# ESPProgrammer.net
KiCad netlist of a schematic drawn in EAGLE
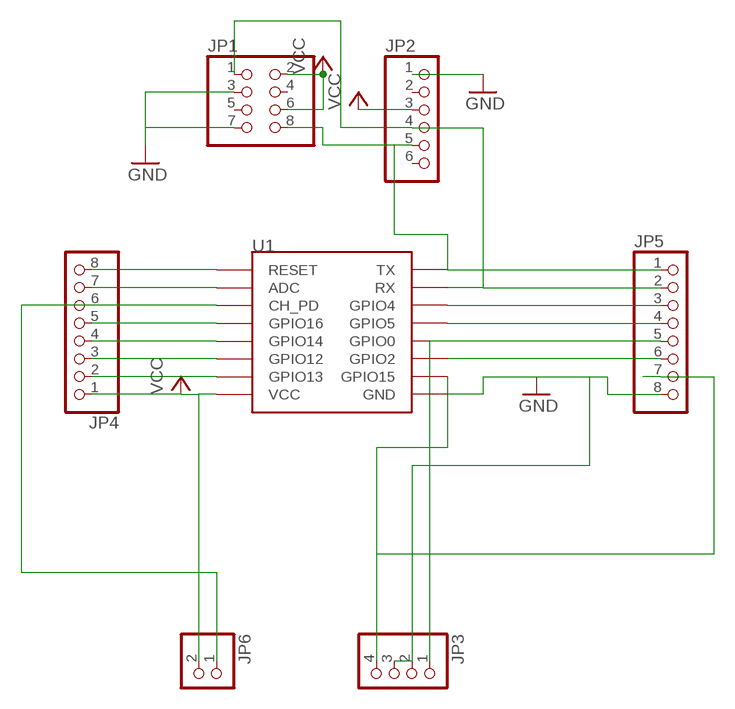
[diagram p0: schematic, sheet 1]

(export (version "E")
  (design (tool "Eeschema 10.0.6"))
  (components
    (comp (ref "JP1")
      (value "PINHD-2X4")
      (footprint "eagle-import:2X04")
      (libsource (lib "eagle-import") (part "PINHD-2X4"))
    )
    (comp (ref "JP2")
      (value "PINHD-1X6")
      (footprint "eagle-import:1X06")
      (libsource (lib "eagle-import") (part "PINHD-1X6"))
    )
    (comp (ref "JP3")
      (value "PINHD-1X4")
      (footprint "eagle-import:1X04")
      (libsource (lib "eagle-import") (part "PINHD-1X4"))
    )
    (comp (ref "JP4")
      (value "PINHD-1X8")
      (footprint "eagle-import:1X08")
      (libsource (lib "eagle-import") (part "PINHD-1X8"))
    )
    (comp (ref "JP5")
      (value "PINHD-1X8")
      (footprint "eagle-import:1X08")
      (libsource (lib "eagle-import") (part "PINHD-1X8"))
    )
    (comp (ref "JP6")
      (value "PINHD-1X2")
      (footprint "eagle-import:1X02")
      (libsource (lib "eagle-import") (part "PINHD-1X2"))
    )
    (comp (ref "U1")
      (value "ESP12")
      (footprint "eagle-import:ESP12")
      (libsource (lib "eagle-import") (part "ESP12"))
    )
  )
  (nets
    (net (code "1") (name "GND") (class "Default")
      (node (ref "JP1") (pin "3") (pinfunction "3_3") (pintype "passive"))
      (node (ref "JP1") (pin "7") (pinfunction "7_7") (pintype "passive"))
      (node (ref "JP2") (pin "1") (pinfunction "1_1") (pintype "passive"))
      (node (ref "JP3") (pin "2") (pinfunction "2_2") (pintype "passive"))
      (node (ref "JP3") (pin "3") (pinfunction "3_3") (pintype "passive"))
      (node (ref "JP5") (pin "8") (pinfunction "8_8") (pintype "passive"))
      (node (ref "U1") (pin "GND") (pinfunction "GND_GND") (pintype "bidirectional"))
    )
    (net (code "2") (name "Net-(JP1-Pad1)") (class "Default")
      (node (ref "JP1") (pin "1") (pinfunction "1_1") (pintype "passive"))
      (node (ref "JP2") (pin "4") (pinfunction "4_4") (pintype "passive"))
      (node (ref "JP5") (pin "2") (pinfunction "2_2") (pintype "passive"))
      (node (ref "U1") (pin "RX") (pinfunction "RX_RX") (pintype "bidirectional"))
    )
    (net (code "3") (name "Net-(JP1-Pad8)") (class "Default")
      (node (ref "JP1") (pin "8") (pinfunction "8_8") (pintype "passive"))
      (node (ref "JP2") (pin "5") (pinfunction "5_5") (pintype "passive"))
      (node (ref "JP5") (pin "1") (pinfunction "1_1") (pintype "passive"))
      (node (ref "U1") (pin "TX") (pinfunction "TX_TX") (pintype "bidirectional"))
    )
    (net (code "4") (name "Net-(JP3-Pad1)") (class "Default")
      (node (ref "JP3") (pin "1") (pinfunction "1_1") (pintype "passive"))
      (node (ref "JP5") (pin "5") (pinfunction "5_5") (pintype "passive"))
      (node (ref "U1") (pin "GPIO0") (pinfunction "GPIO0_GPIO0") (pintype "bidirectional"))
    )
    (net (code "5") (name "Net-(JP3-Pad4)") (class "Default")
      (node (ref "JP3") (pin "4") (pinfunction "4_4") (pintype "passive"))
      (node (ref "JP5") (pin "7") (pinfunction "7_7") (pintype "passive"))
      (node (ref "U1") (pin "GPIO15") (pinfunction "GPIO15_GPIO15") (pintype "bidirectional"))
    )
    (net (code "6") (name "Net-(JP4-Pad2)") (class "Default")
      (node (ref "JP4") (pin "2") (pinfunction "2_2") (pintype "passive"))
      (node (ref "U1") (pin "GPIO13") (pinfunction "GPIO13_GPIO13") (pintype "bidirectional"))
    )
    (net (code "7") (name "Net-(JP4-Pad3)") (class "Default")
      (node (ref "JP4") (pin "3") (pinfunction "3_3") (pintype "passive"))
      (node (ref "U1") (pin "GPIO12") (pinfunction "GPIO12_GPIO12") (pintype "bidirectional"))
    )
    (net (code "8") (name "Net-(JP4-Pad4)") (class "Default")
      (node (ref "JP4") (pin "4") (pinfunction "4_4") (pintype "passive"))
      (node (ref "U1") (pin "GPIO14") (pinfunction "GPIO14_GPIO14") (pintype "bidirectional"))
    )
    (net (code "9") (name "Net-(JP4-Pad5)") (class "Default")
      (node (ref "JP4") (pin "5") (pinfunction "5_5") (pintype "passive"))
      (node (ref "U1") (pin "GPIO16") (pinfunction "GPIO16_GPIO16") (pintype "bidirectional"))
    )
    (net (code "10") (name "Net-(JP4-Pad6)") (class "Default")
      (node (ref "JP4") (pin "6") (pinfunction "6_6") (pintype "passive"))
      (node (ref "JP6") (pin "1") (pinfunction "1_1") (pintype "passive"))
      (node (ref "U1") (pin "CH_PD") (pinfunction "CH_PD_CH_PD") (pintype "bidirectional"))
    )
    (net (code "11") (name "Net-(JP4-Pad7)") (class "Default")
      (node (ref "JP4") (pin "7") (pinfunction "7_7") (pintype "passive"))
      (node (ref "U1") (pin "ADC") (pinfunction "ADC_ADC") (pintype "bidirectional"))
    )
    (net (code "12") (name "Net-(JP4-Pad8)") (class "Default")
      (node (ref "JP4") (pin "8") (pinfunction "8_8") (pintype "passive"))
      (node (ref "U1") (pin "RESET") (pinfunction "RESET_RESET") (pintype "bidirectional"))
    )
    (net (code "13") (name "Net-(JP5-Pad3)") (class "Default")
      (node (ref "JP5") (pin "3") (pinfunction "3_3") (pintype "passive"))
      (node (ref "U1") (pin "GPIO4") (pinfunction "GPIO4_GPIO4") (pintype "bidirectional"))
    )
    (net (code "14") (name "Net-(JP5-Pad4)") (class "Default")
      (node (ref "JP5") (pin "4") (pinfunction "4_4") (pintype "passive"))
      (node (ref "U1") (pin "GPIO5") (pinfunction "GPIO5_GPIO5") (pintype "bidirectional"))
    )
    (net (code "15") (name "Net-(JP5-Pad6)") (class "Default")
      (node (ref "JP5") (pin "6") (pinfunction "6_6") (pintype "passive"))
      (node (ref "U1") (pin "GPIO2") (pinfunction "GPIO2_GPIO2") (pintype "bidirectional"))
    )
    (net (code "16") (name "VCC") (class "Default")
      (node (ref "JP1") (pin "2") (pinfunction "2_2") (pintype "passive"))
      (node (ref "JP1") (pin "6") (pinfunction "6_6") (pintype "passive"))
      (node (ref "JP2") (pin "3") (pinfunction "3_3") (pintype "passive"))
      (node (ref "JP4") (pin "1") (pinfunction "1_1") (pintype "passive"))
      (node (ref "JP6") (pin "2") (pinfunction "2_2") (pintype "passive"))
      (node (ref "U1") (pin "VCC") (pinfunction "VCC_VCC") (pintype "bidirectional"))
    )
    (net (code "17") (name "unconnected-(JP1-Pad4)") (class "Default")
      (node (ref "JP1") (pin "4") (pinfunction "4_4") (pintype "passive"))
    )
    (net (code "18") (name "unconnected-(JP1-Pad5)") (class "Default")
      (node (ref "JP1") (pin "5") (pinfunction "5_5") (pintype "passive"))
    )
    (net (code "19") (name "unconnected-(JP2-Pad2)") (class "Default")
      (node (ref "JP2") (pin "2") (pinfunction "2_2") (pintype "passive"))
    )
    (net (code "20") (name "unconnected-(JP2-Pad6)") (class "Default")
      (node (ref "JP2") (pin "6") (pinfunction "6_6") (pintype "passive"))
    )
  )
)
